# LT3045_3V3.net
KiCad netlist of a schematic drawn in Altium Designer
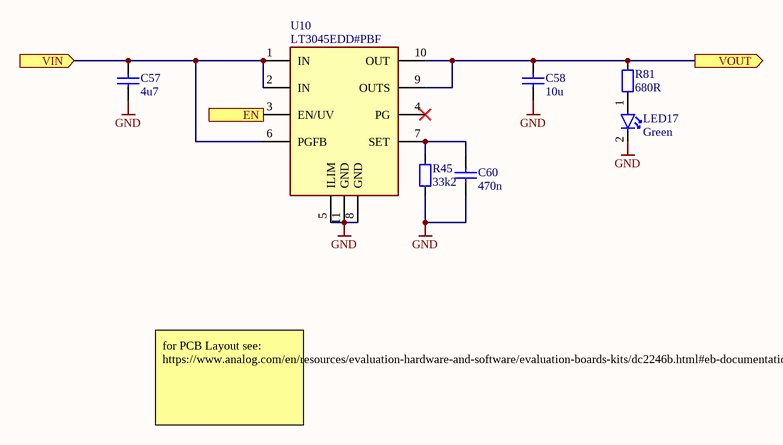
[diagram p0: LT3045_3V3.SchDoc]

(export (version "E")
  (design (tool "Eeschema 10.0.6"))
  (components
    (comp (ref "C57")
      (value "4u7")
      (footprint "C_1206_3216Metric_IPC_N")
      (description "Generic MLCC with 1206 Footprint")
      (libsource (lib "database_library") (part "Capacitor_unpol"))
    )
    (comp (ref "C58")
      (value "10u")
      (footprint "C_1206_3216Metric_IPC_N")
      (description "Generic MLCC with 1206 Footprint")
      (libsource (lib "database_library") (part "Capacitor_unpol"))
    )
    (comp (ref "C60")
      (value "470n")
      (footprint "C_0402_1005Metric_IPC_N")
      (description "Generic MLCC with 0402 Footprint")
      (libsource (lib "database_library") (part "Capacitor_unpol"))
    )
    (comp (ref "LED17")
      (value "Green")
      (footprint "LED_0603_1806Metric_IPC_N")
      (description "MLCC, Low Current, Green, 2.2V, 20mA, 0603")
      (fields
        (field (name "MANUFACTURER") "Broadcom / Avago")
        (field (name "MANUFACTURER PART NUMBER") "HSMG-C190")
      )
      (libsource (lib "database_library") (part "LED"))
    )
    (comp (ref "R45")
      (value "33k2")
      (footprint "R_0402_1005Metric_IPC_N")
      (description "Generic Chip Resistor with 0402 Footprint")
      (libsource (lib "database_library") (part "Resistor"))
    )
    (comp (ref "R81")
      (value "680R")
      (footprint "R_0402_1005Metric_IPC_N")
      (description "Generic Chip Resistor with 0402 Footprint")
      (libsource (lib "database_library") (part "Resistor"))
    )
    (comp (ref "U10")
      (value "LT3045EDD#PBF")
      (footprint "DFN10_3x3")
      (fields (field (name "MANUFACTURER") "Analog Devices"))
      (libsource (lib "database_library") (part "LT3045-10"))
    )
  )
  (nets
    (net (code "1") (name "/EN") (class "Default")
      (node (ref "U10") (pin "3") (pinfunction "EN/UV_3") (pintype "passive"))
    )
    (net (code "2") (name "/VIN") (class "Default")
      (node (ref "C57") (pin "2") (pinfunction "2_2") (pintype "passive"))
      (node (ref "U10") (pin "1") (pinfunction "IN_1") (pintype "passive"))
      (node (ref "U10") (pin "2") (pinfunction "IN_2") (pintype "passive"))
      (node (ref "U10") (pin "6") (pinfunction "PGFB_6") (pintype "passive"))
    )
    (net (code "3") (name "/VOUT") (class "Default")
      (node (ref "C58") (pin "2") (pinfunction "2_2") (pintype "passive"))
      (node (ref "R81") (pin "1") (pinfunction "1_1") (pintype "passive"))
      (node (ref "U10") (pin "10") (pinfunction "OUT_10") (pintype "passive"))
      (node (ref "U10") (pin "9") (pinfunction "OUTS_9") (pintype "passive"))
    )
    (net (code "4") (name "GND") (class "Default")
      (node (ref "C57") (pin "1") (pinfunction "1_1") (pintype "passive"))
      (node (ref "C58") (pin "1") (pinfunction "1_1") (pintype "passive"))
      (node (ref "C60") (pin "1") (pinfunction "1_1") (pintype "passive"))
      (node (ref "LED17") (pin "2") (pinfunction "2_2") (pintype "passive"))
      (node (ref "R45") (pin "1") (pinfunction "1_1") (pintype "passive"))
      (node (ref "U10") (pin "11") (pinfunction "GND_11") (pintype "passive"))
      (node (ref "U10") (pin "5") (pinfunction "ILIM_5") (pintype "passive"))
      (node (ref "U10") (pin "8") (pinfunction "GND_8") (pintype "passive"))
    )
    (net (code "5") (name "Net-(LED17-Pad1)") (class "Default")
      (node (ref "LED17") (pin "1") (pinfunction "1_1") (pintype "passive"))
      (node (ref "R81") (pin "2") (pinfunction "2_2") (pintype "passive"))
    )
    (net (code "6") (name "Net-(U10-SET)") (class "Default")
      (node (ref "C60") (pin "2") (pinfunction "2_2") (pintype "passive"))
      (node (ref "R45") (pin "2") (pinfunction "2_2") (pintype "passive"))
      (node (ref "U10") (pin "7") (pinfunction "SET_7") (pintype "passive"))
    )
    (net (code "7") (name "unconnected-(U10-PG-Pad4)") (class "Default")
      (node (ref "U10") (pin "4") (pinfunction "PG_4") (pintype "passive+no_connect"))
    )
  )
)
